# Primary_Transformer_out.net
KiCad netlist of a schematic drawn in Altium Designer
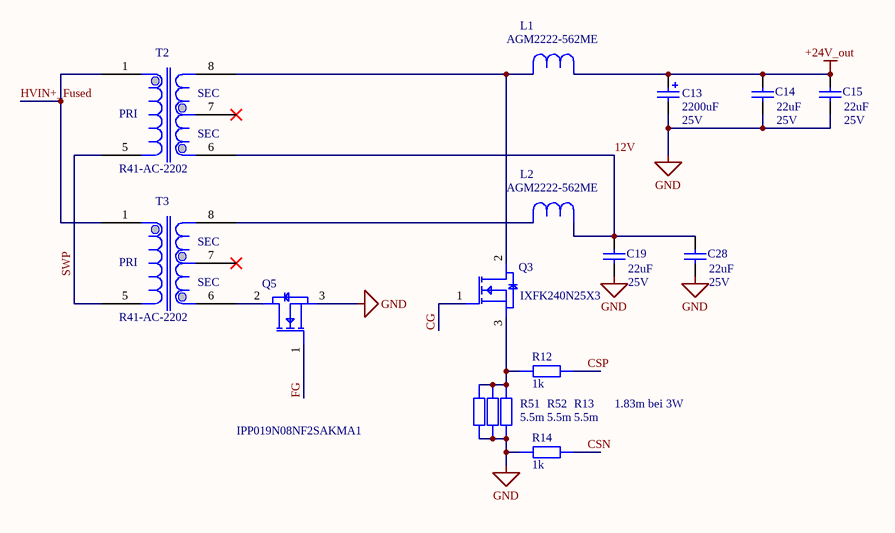
[diagram p0: Primary_Transformer_out.SchDoc]

(export (version "E")
  (design (tool "Eeschema 10.0.6"))
  (components
    (comp (ref "C13")
      (value "~")
      (footprint "WCAP-ATG8_D13H25")
      (description "WCAP-ATG8 Aluminum Electrolytic Capacitor, Radial, THT, D13xH25, 2200uF, 25V")
      (fields
        (field (name "MANUFACTURER PART NUMBER") "860010478021")
        (field (name "MANUFACTURER") "Wurth Elektronik")
        (field (name "CAPACITANCE") "2200uF")
        (field (name "VOLTAGE") "25V")
      )
      (libsource (lib "Altium_WCAP-ATG8 (rev20b)") (part "860010478021"))
    )
    (comp (ref "C14")
      (value "~")
      (footprint "WCAP-CSGP_1210_H=2.5mm")
      (description "WCAP-CSGP Multilayer Ceramic Chip Capacitor, General Purpose, size 1210, X5R, 22uF, 25V")
      (fields
        (field (name "MANUFACTURER PART NUMBER") "885012109014")
        (field (name "MANUFACTURER") "Wurth Elektronik")
        (field (name "CAPACITANCE") "22uF")
        (field (name "VOLTAGE") "25V")
      )
      (libsource (lib "Altium_WCAP-CSGP (rev21d)") (part "885012109014"))
    )
    (comp (ref "C15")
      (value "~")
      (footprint "WCAP-CSGP_1210_H=2.5mm")
      (description "WCAP-CSGP Multilayer Ceramic Chip Capacitor, General Purpose, size 1210, X5R, 22uF, 25V")
      (fields
        (field (name "MANUFACTURER PART NUMBER") "885012109014")
        (field (name "MANUFACTURER") "Wurth Elektronik")
        (field (name "CAPACITANCE") "22uF")
        (field (name "VOLTAGE") "25V")
      )
      (libsource (lib "Altium_WCAP-CSGP (rev21d)") (part "885012109014"))
    )
    (comp (ref "C19")
      (value "~")
      (footprint "WCAP-CSGP_1210_H=2.5mm")
      (description "WCAP-CSGP Multilayer Ceramic Chip Capacitor, General Purpose, size 1210, X5R, 22uF, 25V")
      (fields
        (field (name "MANUFACTURER PART NUMBER") "885012109014")
        (field (name "MANUFACTURER") "Wurth Elektronik")
        (field (name "CAPACITANCE") "22uF")
        (field (name "VOLTAGE") "25V")
      )
      (libsource (lib "Altium_WCAP-CSGP (rev21d)") (part "885012109014"))
    )
    (comp (ref "C28")
      (value "~")
      (footprint "WCAP-CSGP_1210_H=2.5mm")
      (description "WCAP-CSGP Multilayer Ceramic Chip Capacitor, General Purpose, size 1210, X5R, 22uF, 25V")
      (fields
        (field (name "MANUFACTURER PART NUMBER") "885012109014")
        (field (name "MANUFACTURER") "Wurth Elektronik")
        (field (name "CAPACITANCE") "22uF")
        (field (name "VOLTAGE") "25V")
      )
      (libsource (lib "Altium_WCAP-CSGP (rev21d)") (part "885012109014"))
    )
    (comp (ref "L1")
      (value "AGM2222-562ME")
      (footprint "AGM2222-562")
      (description "Shielded Power Inductors")
      (libsource (lib "Integrated_LibraryLukas_New") (part "AGM2222-562ME"))
    )
    (comp (ref "L2")
      (value "AGM2222-562ME")
      (footprint "AGM2222-562")
      (description "Shielded Power Inductors")
      (libsource (lib "Integrated_LibraryLukas_New") (part "AGM2222-562ME"))
    )
    (comp (ref "Q3")
      (value "IXFK240N25X3")
      (footprint "IXFK240N25X3_w_Cooler")
      (description "Mosfet N-ch 250V 240A TO264")
      (fields (field (name "MANUFACTURER") "IXYS"))
      (libsource (lib "Integrated_LibraryLukas_New") (part "IXFK240N25X3"))
    )
    (comp (ref "Q5")
      (value "IPP019N08NF2SAKMA1")
      (footprint "IPP019N08NF2SAKMA1_w_Cooler")
      (description "Transistor Power MOSFET N-Channel 80V 191A 3-Pin TO-220 Tube")
      (fields (field (name "MANUFACTURER") "Infineon"))
      (libsource (lib "Integrated_LibraryLukas_New") (part "IPP019N08NF2SAKMA1"))
    )
    (comp (ref "R12")
      (value "1k")
      (footprint "STACKPOLE CSR1206")
      (description "Resistor with multiple footprints")
      (fields (field (name "Comment") "SMD Resistor"))
      (libsource (lib "Standardbauteile") (part "SMD Resistor"))
    )
    (comp (ref "R13")
      (value "5.5m")
      (footprint "STACKPOLE CSR1206")
      (description "Resistor with multiple footprints")
      (libsource (lib "Standardbauteile") (part "SMD Resistor"))
    )
    (comp (ref "R14")
      (value "1k")
      (footprint "STACKPOLE CSR1206")
      (description "Resistor with multiple footprints")
      (fields (field (name "Comment") "SMD Resistor"))
      (libsource (lib "Standardbauteile") (part "SMD Resistor"))
    )
    (comp (ref "R51")
      (value "5.5m")
      (footprint "STACKPOLE CSR1206")
      (description "Resistor with multiple footprints")
      (libsource (lib "Standardbauteile") (part "SMD Resistor"))
    )
    (comp (ref "R52")
      (value "5.5m")
      (footprint "STACKPOLE CSR1206")
      (description "Resistor with multiple footprints")
      (libsource (lib "Standardbauteile") (part "SMD Resistor"))
    )
    (comp (ref "T2")
      (value "R41-AC-2202")
      (footprint "R41-AC-2202 Landing Pattern")
      (description "High Voltage Transformer")
      (libsource (lib "Integrated_LibraryLukas_New") (part "R41-AC-2202"))
    )
    (comp (ref "T3")
      (value "R41-AC-2202")
      (footprint "R41-AC-2202 Landing Pattern")
      (description "High Voltage Transformer")
      (libsource (lib "Integrated_LibraryLukas_New") (part "R41-AC-2202"))
    )
  )
  (nets
    (net (code "1") (name "+24V_out") (class "Default")
      (node (ref "C13") (pin "1") (pinfunction "P_1") (pintype "passive"))
      (node (ref "C14") (pin "1") (pinfunction "1_1") (pintype "passive"))
      (node (ref "C15") (pin "1") (pinfunction "1_1") (pintype "passive"))
      (node (ref "L1") (pin "2") (pintype "passive"))
    )
    (net (code "2") (name "/12V") (class "Default")
      (node (ref "C19") (pin "1") (pinfunction "1_1") (pintype "passive"))
      (node (ref "C28") (pin "1") (pinfunction "1_1") (pintype "passive"))
      (node (ref "L2") (pin "2") (pintype "passive"))
      (node (ref "T2") (pin "6") (pintype "passive"))
    )
    (net (code "3") (name "/CG") (class "Default") (node (ref "Q3") (pin "1") (pintype "input")))
    (net (code "4") (name "/CSN") (class "Default")
      (node (ref "R14") (pin "2") (pinfunction "2_2") (pintype "passive"))
    )
    (net (code "5") (name "/CSP") (class "Default")
      (node (ref "R12") (pin "2") (pinfunction "2_2") (pintype "passive"))
    )
    (net (code "6") (name "/FG") (class "Default") (node (ref "Q5") (pin "1") (pintype "input")))
    (net (code "7") (name "/HVIN+_Fused") (class "Default")
      (node (ref "T2") (pin "1") (pintype "passive"))
      (node (ref "T3") (pin "1") (pintype "passive"))
    )
    (net (code "8") (name "/SWP") (class "Default")
      (node (ref "T2") (pin "5") (pintype "passive"))
      (node (ref "T3") (pin "5") (pintype "passive"))
    )
    (net (code "9") (name "GND") (class "Default")
      (node (ref "C13") (pin "2") (pinfunction "N_2") (pintype "passive"))
      (node (ref "C14") (pin "2") (pinfunction "2_2") (pintype "passive"))
      (node (ref "C15") (pin "2") (pinfunction "2_2") (pintype "passive"))
      (node (ref "C19") (pin "2") (pinfunction "2_2") (pintype "passive"))
      (node (ref "C28") (pin "2") (pinfunction "2_2") (pintype "passive"))
      (node (ref "Q5") (pin "3") (pintype "input"))
      (node (ref "R13") (pin "1") (pinfunction "1_1") (pintype "passive"))
      (node (ref "R14") (pin "1") (pinfunction "1_1") (pintype "passive"))
      (node (ref "R51") (pin "1") (pinfunction "1_1") (pintype "passive"))
      (node (ref "R52") (pin "1") (pinfunction "1_1") (pintype "passive"))
    )
    (net (code "10") (name "Net-(L1-Pad1)") (class "Default")
      (node (ref "L1") (pin "1") (pintype "passive"))
      (node (ref "Q3") (pin "2") (pintype "input"))
      (node (ref "T2") (pin "8") (pintype "passive"))
    )
    (net (code "11") (name "Net-(L2-Pad1)") (class "Default")
      (node (ref "L2") (pin "1") (pintype "passive"))
      (node (ref "T3") (pin "8") (pintype "passive"))
    )
    (net (code "12") (name "Net-(Q3-Pad3)") (class "Default")
      (node (ref "Q3") (pin "3") (pintype "input"))
      (node (ref "R12") (pin "1") (pinfunction "1_1") (pintype "passive"))
      (node (ref "R13") (pin "2") (pinfunction "2_2") (pintype "passive"))
      (node (ref "R51") (pin "2") (pinfunction "2_2") (pintype "passive"))
      (node (ref "R52") (pin "2") (pinfunction "2_2") (pintype "passive"))
    )
    (net (code "13") (name "Net-(Q5-Pad2)") (class "Default")
      (node (ref "Q5") (pin "2") (pintype "input"))
      (node (ref "T3") (pin "6") (pintype "passive"))
    )
    (net (code "14") (name "unconnected-(T2-Pad7)") (class "Default")
      (node (ref "T2") (pin "7") (pintype "passive+no_connect"))
    )
    (net (code "15") (name "unconnected-(T3-Pad7)") (class "Default")
      (node (ref "T3") (pin "7") (pintype "passive+no_connect"))
    )
  )
)
